# MCU.net
KiCad netlist of a schematic drawn in Altium Designer
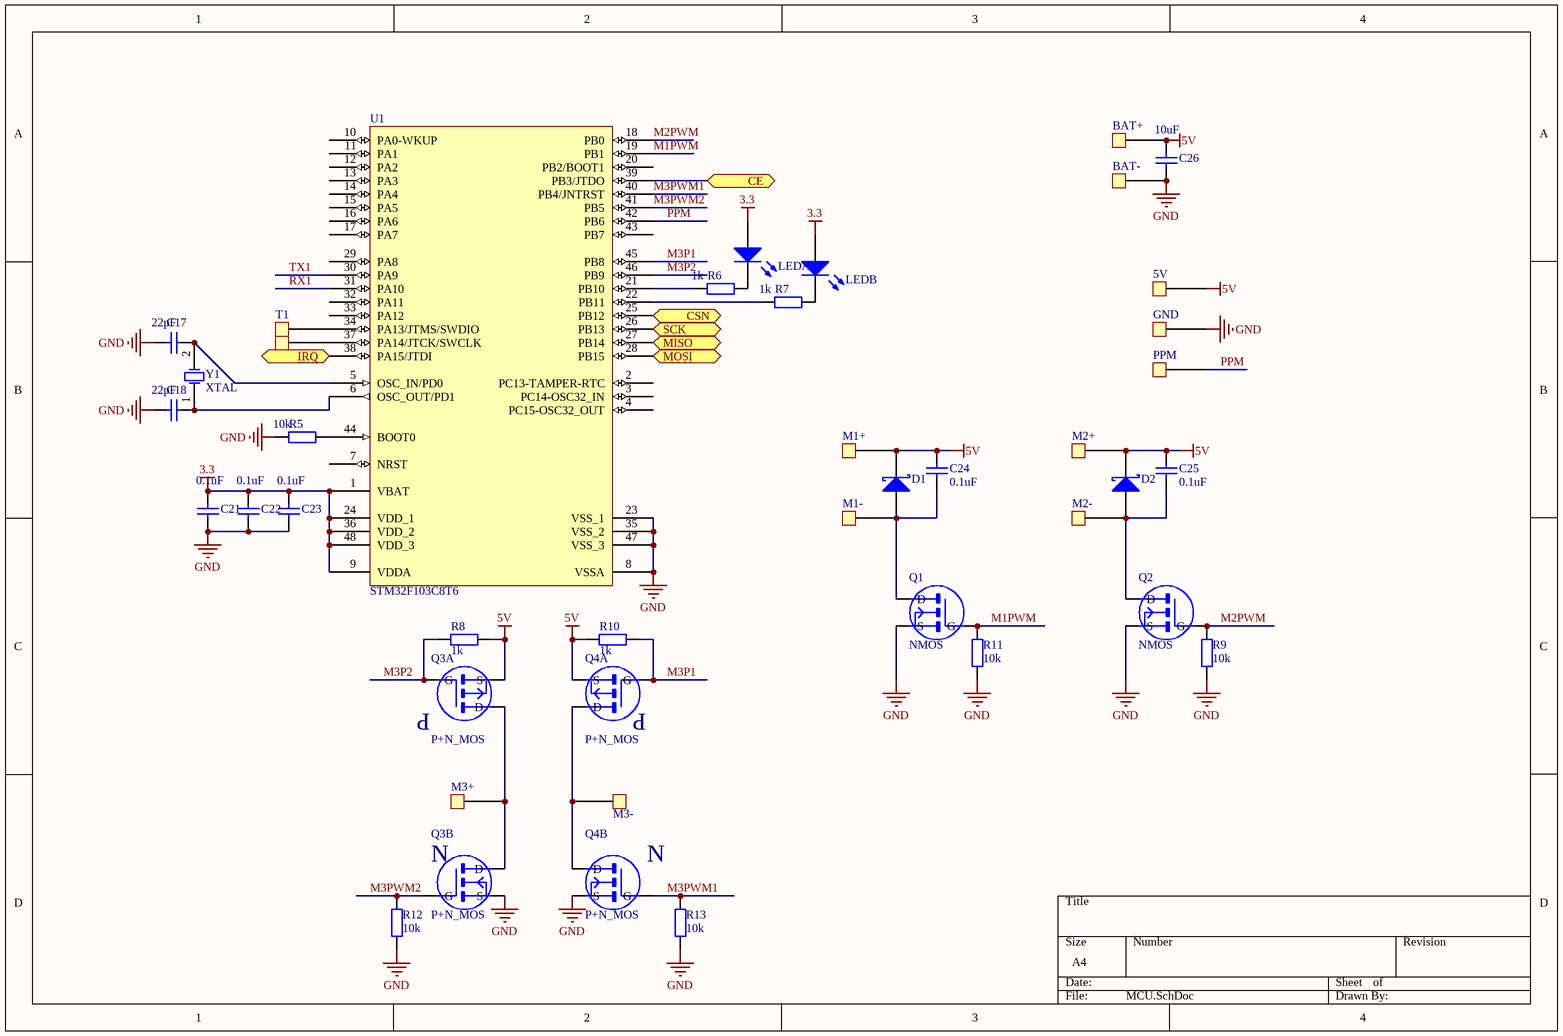
[diagram p0: MCU.SchDoc]

(export (version "E")
  (design (tool "Eeschema 10.0.6"))
  (components
    (comp (ref "5V") (value "TestPad") (footprint "TestPad") (libsource (lib "sch") (part "TestPad")))
    (comp (ref "BAT+") (value "TestPad") (footprint "TestPad") (libsource (lib "sch") (part "TestPad")))
    (comp (ref "BAT-") (value "TestPad") (footprint "TestPad") (libsource (lib "sch") (part "TestPad")))
    (comp (ref "C17")
      (value "22pF")
      (footprint "0402")
      (description "Capacitor")
      (fields (field (name "PUBLISHER") "Altium Limited"))
      (libsource (lib "RTC6705") (part "Cap"))
    )
    (comp (ref "C18")
      (value "22pF")
      (footprint "0402")
      (description "Capacitor")
      (fields (field (name "PUBLISHER") "Altium Limited"))
      (libsource (lib "RTC6705") (part "Cap"))
    )
    (comp (ref "C21")
      (value "0.1uF")
      (footprint "0402")
      (description "Capacitor")
      (fields (field (name "PUBLISHER") "Altium Limited"))
      (libsource (lib "RTC6705") (part "Cap"))
    )
    (comp (ref "C22")
      (value "0.1uF")
      (footprint "0402")
      (description "Capacitor")
      (fields (field (name "PUBLISHER") "Altium Limited"))
      (libsource (lib "RTC6705") (part "Cap"))
    )
    (comp (ref "C23")
      (value "0.1uF")
      (footprint "0402")
      (description "Capacitor")
      (fields (field (name "PUBLISHER") "Altium Limited"))
      (libsource (lib "RTC6705") (part "Cap"))
    )
    (comp (ref "C24")
      (value "0.1uF")
      (footprint "0402")
      (description "Capacitor")
      (fields (field (name "PUBLISHER") "Altium Limited"))
      (libsource (lib "RTC6705") (part "Cap"))
    )
    (comp (ref "C25")
      (value "0.1uF")
      (footprint "0402")
      (description "Capacitor")
      (fields (field (name "PUBLISHER") "Altium Limited"))
      (libsource (lib "RTC6705") (part "Cap"))
    )
    (comp (ref "C26")
      (value "10uF")
      (footprint "0603")
      (description "Capacitor")
      (fields (field (name "PUBLISHER") "Altium Limited"))
      (libsource (lib "RTC6705") (part "Cap"))
    )
    (comp (ref "D1")
      (value "Diode BAT17")
      (footprint "LC-SOD-323")
      (description "Silicon RF Schottky Diode for Mixer Applications in the VHF/UHF Range")
      (fields (field (name "PUBLISHER") "Altium Limited"))
      (libsource (lib "Miscellaneous Devices") (part "Diode BAT17"))
    )
    (comp (ref "D2")
      (value "Diode BAT17")
      (footprint "LC-SOD-323")
      (description "Silicon RF Schottky Diode for Mixer Applications in the VHF/UHF Range")
      (fields (field (name "PUBLISHER") "Altium Limited"))
      (libsource (lib "Miscellaneous Devices") (part "Diode BAT17"))
    )
    (comp (ref "GND") (value "TestPad") (footprint "TestPad") (libsource (lib "sch") (part "TestPad")))
    (comp (ref "LED")
      (value "LEDx2")
      (footprint "LC-0603_Rx2")
      (description "Typical RED GaAs LED")
      (fields (field (name "PUBLISHER") "Altium Limited"))
      (libsource (lib "sch") (part "LEDx2"))
    )
    (comp (ref "M1+") (value "TestPad") (footprint "TestPad") (libsource (lib "sch") (part "TestPad")))
    (comp (ref "M1-") (value "TestPad") (footprint "TestPad") (libsource (lib "sch") (part "TestPad")))
    (comp (ref "M2+") (value "TestPad") (footprint "TestPad") (libsource (lib "sch") (part "TestPad")))
    (comp (ref "M2-") (value "TestPad") (footprint "TestPad") (libsource (lib "sch") (part "TestPad")))
    (comp (ref "M3+") (value "TestPad") (footprint "TestPad") (libsource (lib "sch") (part "TestPad")))
    (comp (ref "M3-") (value "TestPad") (footprint "TestPad") (libsource (lib "") (part "TestPad_1")))
    (comp (ref "PPM") (value "TestPad") (footprint "TestPad") (libsource (lib "sch") (part "TestPad")))
    (comp (ref "Q1") (value "NMOS") (footprint "SOT-23B_L") (libsource (lib "sch") (part "NMOS")))
    (comp (ref "Q2") (value "NMOS") (footprint "SOT-23B_L") (libsource (lib "sch") (part "NMOS")))
    (comp (ref "Q3") (value "P+N_MOS") (footprint "SOT23-6") (libsource (lib "") (part "P+N_MOS_1")))
    (comp (ref "Q4") (value "P+N_MOS") (footprint "SOT23-6") (libsource (lib "") (part "P+N_MOS_1")))
    (comp (ref "R5")
      (value "10k")
      (footprint "0402")
      (description "Resistor")
      (fields (field (name "PUBLISHER") "Altium Limited"))
      (libsource (lib "") (part "Res2_1"))
    )
    (comp (ref "R6")
      (value "1k")
      (footprint "0402")
      (description "Resistor")
      (fields (field (name "PUBLISHER") "Altium Limited"))
      (libsource (lib "") (part "Res2_1"))
    )
    (comp (ref "R7")
      (value "1k")
      (footprint "0402")
      (description "Resistor")
      (fields (field (name "PUBLISHER") "Altium Limited"))
      (libsource (lib "") (part "Res2_1"))
    )
    (comp (ref "R8")
      (value "1k")
      (footprint "0402")
      (description "Resistor")
      (fields (field (name "PUBLISHER") "Altium Limited"))
      (libsource (lib "") (part "Res2_2"))
    )
    (comp (ref "R9")
      (value "10k")
      (footprint "0402")
      (description "Resistor")
      (fields (field (name "PUBLISHER") "Altium Limited"))
      (libsource (lib "RTC6705") (part "Res2"))
    )
    (comp (ref "R10")
      (value "1k")
      (footprint "0402")
      (description "Resistor")
      (fields (field (name "PUBLISHER") "Altium Limited"))
      (libsource (lib "") (part "Res2_2"))
    )
    (comp (ref "R11")
      (value "10k")
      (footprint "0402")
      (description "Resistor")
      (fields (field (name "PUBLISHER") "Altium Limited"))
      (libsource (lib "RTC6705") (part "Res2"))
    )
    (comp (ref "R12")
      (value "10k")
      (footprint "0402")
      (description "Resistor")
      (fields (field (name "PUBLISHER") "Altium Limited"))
      (libsource (lib "RTC6705") (part "Res2"))
    )
    (comp (ref "R13")
      (value "10k")
      (footprint "0402")
      (description "Resistor")
      (fields (field (name "PUBLISHER") "Altium Limited"))
      (libsource (lib "RTC6705") (part "Res2"))
    )
    (comp (ref "T1") (value "TestPad") (footprint "TestPad - 1mm") (libsource (lib "sch") (part "TestPad")))
    (comp (ref "T2") (value "TestPad") (footprint "TestPad - 1mm") (libsource (lib "sch") (part "TestPad")))
    (comp (ref "U1")
      (value "STM32F103C8T6")
      (footprint "LQFP48_L")
      (description "STM32 ARM-based 32-bit MCU with 64 Kbytes Flash, 48-pin LQFP, Industrial Temperature")
      (fields (field (name "PUBLISHER") "*"))
      (libsource (lib "ST Microcontroller 32-Bit STM32 SCH") (part "STM32F103C8T6"))
    )
    (comp (ref "Y1")
      (value "XTAL")
      (footprint "5032-crystal")
      (description "Crystal Oscillator")
      (fields (field (name "PUBLISHER") "Altium Limited"))
      (libsource (lib "Miscellaneous Devices") (part "XTAL"))
    )
  )
  (nets
    (net (code "1") (name "/CE") (class "Default")
      (node (ref "U1") (pin "39") (pinfunction "PB3/JTDO_39") (pintype "bidirectional"))
    )
    (net (code "2") (name "/CSN") (class "Default")
      (node (ref "U1") (pin "25") (pinfunction "PB12_25") (pintype "bidirectional"))
    )
    (net (code "3") (name "/IRQ") (class "Default")
      (node (ref "U1") (pin "38") (pinfunction "PA15/JTDI_38") (pintype "bidirectional"))
    )
    (net (code "4") (name "/M1PWM") (class "Default")
      (node (ref "Q1") (pin "G") (pinfunction "G_G") (pintype "passive"))
      (node (ref "R11") (pin "2") (pinfunction "2_2") (pintype "passive"))
      (node (ref "U1") (pin "19") (pinfunction "PB1_19") (pintype "bidirectional"))
    )
    (net (code "5") (name "/M2PWM") (class "Default")
      (node (ref "Q2") (pin "G") (pinfunction "G_G") (pintype "passive"))
      (node (ref "R9") (pin "2") (pinfunction "2_2") (pintype "passive"))
      (node (ref "U1") (pin "18") (pinfunction "PB0_18") (pintype "bidirectional"))
    )
    (net (code "6") (name "/M3P1") (class "Default")
      (node (ref "Q4") (pin "3") (pinfunction "G_3") (pintype "passive"))
      (node (ref "R10") (pin "1") (pinfunction "1_1") (pintype "passive"))
      (node (ref "U1") (pin "45") (pinfunction "PB8_45") (pintype "bidirectional"))
    )
    (net (code "7") (name "/M3P2") (class "Default")
      (node (ref "Q3") (pin "3") (pinfunction "G_3") (pintype "passive"))
      (node (ref "R8") (pin "2") (pinfunction "2_2") (pintype "passive"))
      (node (ref "U1") (pin "46") (pinfunction "PB9_46") (pintype "bidirectional"))
    )
    (net (code "8") (name "/M3PWM1") (class "Default")
      (node (ref "Q4") (pin "1") (pinfunction "G_1") (pintype "passive"))
      (node (ref "R13") (pin "2") (pinfunction "2_2") (pintype "passive"))
      (node (ref "U1") (pin "40") (pinfunction "PB4/JNTRST_40") (pintype "bidirectional"))
    )
    (net (code "9") (name "/M3PWM2") (class "Default")
      (node (ref "Q3") (pin "1") (pinfunction "G_1") (pintype "passive"))
      (node (ref "R12") (pin "2") (pinfunction "2_2") (pintype "passive"))
      (node (ref "U1") (pin "41") (pinfunction "PB5_41") (pintype "bidirectional"))
    )
    (net (code "10") (name "/MISO") (class "Default")
      (node (ref "U1") (pin "27") (pinfunction "PB14_27") (pintype "bidirectional"))
    )
    (net (code "11") (name "/MOSI") (class "Default")
      (node (ref "U1") (pin "28") (pinfunction "PB15_28") (pintype "bidirectional"))
    )
    (net (code "12") (name "/PPM") (class "Default")
      (node (ref "PPM") (pin "1") (pinfunction "3_1") (pintype "passive"))
      (node (ref "U1") (pin "42") (pinfunction "PB6_42") (pintype "bidirectional"))
    )
    (net (code "13") (name "/RX1") (class "Default")
      (node (ref "U1") (pin "31") (pinfunction "PA10_31") (pintype "bidirectional"))
    )
    (net (code "14") (name "/SCK") (class "Default")
      (node (ref "U1") (pin "26") (pinfunction "PB13_26") (pintype "bidirectional"))
    )
    (net (code "15") (name "/TX1") (class "Default")
      (node (ref "U1") (pin "30") (pinfunction "PA9_30") (pintype "bidirectional"))
    )
    (net (code "16") (name "3.3") (class "Default")
      (node (ref "C21") (pin "1") (pinfunction "1_1") (pintype "passive"))
      (node (ref "C22") (pin "1") (pinfunction "1_1") (pintype "passive"))
      (node (ref "C23") (pin "1") (pinfunction "1_1") (pintype "passive"))
      (node (ref "LED") (pin "1") (pinfunction "A_1") (pintype "passive"))
      (node (ref "LED") (pin "2") (pinfunction "A_2") (pintype "passive"))
      (node (ref "U1") (pin "1") (pinfunction "VBAT_1") (pintype "power_in"))
      (node (ref "U1") (pin "24") (pinfunction "VDD_1_24") (pintype "power_in"))
      (node (ref "U1") (pin "36") (pinfunction "VDD_2_36") (pintype "power_in"))
      (node (ref "U1") (pin "48") (pinfunction "VDD_3_48") (pintype "power_in"))
      (node (ref "U1") (pin "9") (pinfunction "VDDA_9") (pintype "power_in"))
    )
    (net (code "17") (name "5V") (class "Default")
      (node (ref "5V") (pin "1") (pinfunction "3_1") (pintype "passive"))
      (node (ref "BAT+") (pin "1") (pinfunction "3_1") (pintype "passive"))
      (node (ref "C24") (pin "2") (pinfunction "2_2") (pintype "passive"))
      (node (ref "C25") (pin "2") (pinfunction "2_2") (pintype "passive"))
      (node (ref "C26") (pin "1") (pinfunction "1_1") (pintype "passive"))
      (node (ref "D1") (pin "3") (pinfunction "K_3") (pintype "passive"))
      (node (ref "D2") (pin "3") (pinfunction "K_3") (pintype "passive"))
      (node (ref "M1+") (pin "1") (pinfunction "3_1") (pintype "passive"))
      (node (ref "M2+") (pin "1") (pinfunction "3_1") (pintype "passive"))
      (node (ref "Q3") (pin "2") (pinfunction "S_2") (pintype "passive"))
      (node (ref "Q4") (pin "2") (pinfunction "S_2") (pintype "passive"))
      (node (ref "R10") (pin "2") (pinfunction "2_2") (pintype "passive"))
      (node (ref "R8") (pin "1") (pinfunction "1_1") (pintype "passive"))
    )
    (net (code "18") (name "GND") (class "Default")
      (node (ref "BAT-") (pin "1") (pinfunction "3_1") (pintype "passive"))
      (node (ref "C17") (pin "1") (pinfunction "1_1") (pintype "passive"))
      (node (ref "C18") (pin "1") (pinfunction "1_1") (pintype "passive"))
      (node (ref "C21") (pin "2") (pinfunction "2_2") (pintype "passive"))
      (node (ref "C22") (pin "2") (pinfunction "2_2") (pintype "passive"))
      (node (ref "C23") (pin "2") (pinfunction "2_2") (pintype "passive"))
      (node (ref "C26") (pin "2") (pinfunction "2_2") (pintype "passive"))
      (node (ref "GND") (pin "1") (pinfunction "3_1") (pintype "passive"))
      (node (ref "Q1") (pin "S") (pinfunction "S_S") (pintype "passive"))
      (node (ref "Q2") (pin "S") (pinfunction "S_S") (pintype "passive"))
      (node (ref "Q3") (pin "5") (pinfunction "S_5") (pintype "passive"))
      (node (ref "Q4") (pin "5") (pinfunction "S_5") (pintype "passive"))
      (node (ref "R11") (pin "1") (pinfunction "1_1") (pintype "passive"))
      (node (ref "R12") (pin "1") (pinfunction "1_1") (pintype "passive"))
      (node (ref "R13") (pin "1") (pinfunction "1_1") (pintype "passive"))
      (node (ref "R5") (pin "1") (pinfunction "1_1") (pintype "passive"))
      (node (ref "R9") (pin "1") (pinfunction "1_1") (pintype "passive"))
      (node (ref "U1") (pin "23") (pinfunction "VSS_1_23") (pintype "power_in"))
      (node (ref "U1") (pin "35") (pinfunction "VSS_2_35") (pintype "power_in"))
      (node (ref "U1") (pin "47") (pinfunction "VSS_3_47") (pintype "power_in"))
      (node (ref "U1") (pin "8") (pinfunction "VSSA_8") (pintype "power_in"))
    )
    (net (code "19") (name "Net-(D1-A)") (class "Default")
      (node (ref "C24") (pin "1") (pinfunction "1_1") (pintype "passive"))
      (node (ref "D1") (pin "1") (pinfunction "A_1") (pintype "passive"))
      (node (ref "M1-") (pin "1") (pinfunction "3_1") (pintype "passive"))
      (node (ref "Q1") (pin "D") (pinfunction "D_D") (pintype "passive"))
    )
    (net (code "20") (name "Net-(D2-A)") (class "Default")
      (node (ref "C25") (pin "1") (pinfunction "1_1") (pintype "passive"))
      (node (ref "D2") (pin "1") (pinfunction "A_1") (pintype "passive"))
      (node (ref "M2-") (pin "1") (pinfunction "3_1") (pintype "passive"))
      (node (ref "Q2") (pin "D") (pinfunction "D_D") (pintype "passive"))
    )
    (net (code "21") (name "Net-(LEDA-K)") (class "Default")
      (node (ref "LED") (pin "3") (pinfunction "K_3") (pintype "passive"))
      (node (ref "R6") (pin "2") (pinfunction "2_2") (pintype "passive"))
    )
    (net (code "22") (name "Net-(LEDB-K)") (class "Default")
      (node (ref "LED") (pin "4") (pinfunction "K_4") (pintype "passive"))
      (node (ref "R7") (pin "2") (pinfunction "2_2") (pintype "passive"))
    )
    (net (code "23") (name "Net-(M3+-3)") (class "Default")
      (node (ref "M3+") (pin "1") (pinfunction "3_1") (pintype "passive"))
      (node (ref "Q3") (pin "4") (pinfunction "D_4") (pintype "passive"))
      (node (ref "Q3") (pin "6") (pinfunction "D_6") (pintype "passive"))
    )
    (net (code "24") (name "Net-(M3--3)") (class "Default")
      (node (ref "M3-") (pin "1") (pinfunction "3_1") (pintype "passive"))
      (node (ref "Q4") (pin "4") (pinfunction "D_4") (pintype "passive"))
      (node (ref "Q4") (pin "6") (pinfunction "D_6") (pintype "passive"))
    )
    (net (code "25") (name "Net-(T1-3)") (class "Default")
      (node (ref "T1") (pin "1") (pinfunction "3_1") (pintype "passive"))
      (node (ref "U1") (pin "34") (pinfunction "PA13/JTMS/SWDIO_34") (pintype "bidirectional"))
    )
    (net (code "26") (name "Net-(T2-3)") (class "Default")
      (node (ref "T2") (pin "1") (pinfunction "3_1") (pintype "passive"))
      (node (ref "U1") (pin "37") (pinfunction "PA14/JTCK/SWCLK_37") (pintype "bidirectional"))
    )
    (net (code "27") (name "Net-(U1-BOOT0)") (class "Default")
      (node (ref "R5") (pin "2") (pinfunction "2_2") (pintype "passive"))
      (node (ref "U1") (pin "44") (pinfunction "BOOT0_44") (pintype "input"))
    )
    (net (code "28") (name "Net-(U1-OSC_IN{slash}PD0)") (class "Default")
      (node (ref "C17") (pin "2") (pinfunction "2_2") (pintype "passive"))
      (node (ref "U1") (pin "5") (pinfunction "OSC_IN/PD0_5") (pintype "input"))
      (node (ref "Y1") (pin "2") (pinfunction "OSC2_2") (pintype "passive"))
    )
    (net (code "29") (name "Net-(U1-OSC_OUT{slash}PD1)") (class "Default")
      (node (ref "C18") (pin "2") (pinfunction "2_2") (pintype "passive"))
      (node (ref "U1") (pin "6") (pinfunction "OSC_OUT/PD1_6") (pintype "output"))
      (node (ref "Y1") (pin "1") (pinfunction "OSC1_1") (pintype "passive"))
    )
    (net (code "30") (name "Net-(U1-PB10)") (class "Default")
      (node (ref "R6") (pin "1") (pinfunction "1_1") (pintype "passive"))
      (node (ref "U1") (pin "21") (pinfunction "PB10_21") (pintype "bidirectional"))
    )
    (net (code "31") (name "Net-(U1-PB11)") (class "Default")
      (node (ref "R7") (pin "1") (pinfunction "1_1") (pintype "passive"))
      (node (ref "U1") (pin "22") (pinfunction "PB11_22") (pintype "bidirectional"))
    )
    (net (code "32") (name "unconnected-(U1-NRST-Pad7)") (class "Default")
      (node (ref "U1") (pin "7") (pinfunction "NRST_7") (pintype "bidirectional"))
    )
    (net (code "33") (name "unconnected-(U1-PA0-WKUP-Pad10)") (class "Default")
      (node (ref "U1") (pin "10") (pinfunction "PA0-WKUP_10") (pintype "bidirectional"))
    )
    (net (code "34") (name "unconnected-(U1-PA1-Pad11)") (class "Default")
      (node (ref "U1") (pin "11") (pinfunction "PA1_11") (pintype "bidirectional"))
    )
    (net (code "35") (name "unconnected-(U1-PA2-Pad12)") (class "Default")
      (node (ref "U1") (pin "12") (pinfunction "PA2_12") (pintype "bidirectional"))
    )
    (net (code "36") (name "unconnected-(U1-PA3-Pad13)") (class "Default")
      (node (ref "U1") (pin "13") (pinfunction "PA3_13") (pintype "bidirectional"))
    )
    (net (code "37") (name "unconnected-(U1-PA4-Pad14)") (class "Default")
      (node (ref "U1") (pin "14") (pinfunction "PA4_14") (pintype "bidirectional"))
    )
    (net (code "38") (name "unconnected-(U1-PA5-Pad15)") (class "Default")
      (node (ref "U1") (pin "15") (pinfunction "PA5_15") (pintype "bidirectional"))
    )
    (net (code "39") (name "unconnected-(U1-PA6-Pad16)") (class "Default")
      (node (ref "U1") (pin "16") (pinfunction "PA6_16") (pintype "bidirectional"))
    )
    (net (code "40") (name "unconnected-(U1-PA7-Pad17)") (class "Default")
      (node (ref "U1") (pin "17") (pinfunction "PA7_17") (pintype "bidirectional"))
    )
    (net (code "41") (name "unconnected-(U1-PA8-Pad29)") (class "Default")
      (node (ref "U1") (pin "29") (pinfunction "PA8_29") (pintype "bidirectional"))
    )
    (net (code "42") (name "unconnected-(U1-PA11-Pad32)") (class "Default")
      (node (ref "U1") (pin "32") (pinfunction "PA11_32") (pintype "bidirectional"))
    )
    (net (code "43") (name "unconnected-(U1-PA12-Pad33)") (class "Default")
      (node (ref "U1") (pin "33") (pinfunction "PA12_33") (pintype "bidirectional"))
    )
    (net (code "44") (name "unconnected-(U1-PB2{slash}BOOT1-Pad20)") (class "Default")
      (node (ref "U1") (pin "20") (pinfunction "PB2/BOOT1_20") (pintype "bidirectional"))
    )
    (net (code "45") (name "unconnected-(U1-PB7-Pad43)") (class "Default")
      (node (ref "U1") (pin "43") (pinfunction "PB7_43") (pintype "bidirectional"))
    )
    (net (code "46") (name "unconnected-(U1-PC13-TAMPER-RTC-Pad2)") (class "Default")
      (node (ref "U1") (pin "2") (pinfunction "PC13-TAMPER-RTC_2") (pintype "bidirectional"))
    )
    (net (code "47") (name "unconnected-(U1-PC14-OSC32_IN-Pad3)") (class "Default")
      (node (ref "U1") (pin "3") (pinfunction "PC14-OSC32_IN_3") (pintype "bidirectional"))
    )
    (net (code "48") (name "unconnected-(U1-PC15-OSC32_OUT-Pad4)") (class "Default")
      (node (ref "U1") (pin "4") (pinfunction "PC15-OSC32_OUT_4") (pintype "bidirectional"))
    )
  )
)
